# display.net
KiCad netlist of a schematic drawn in EAGLE
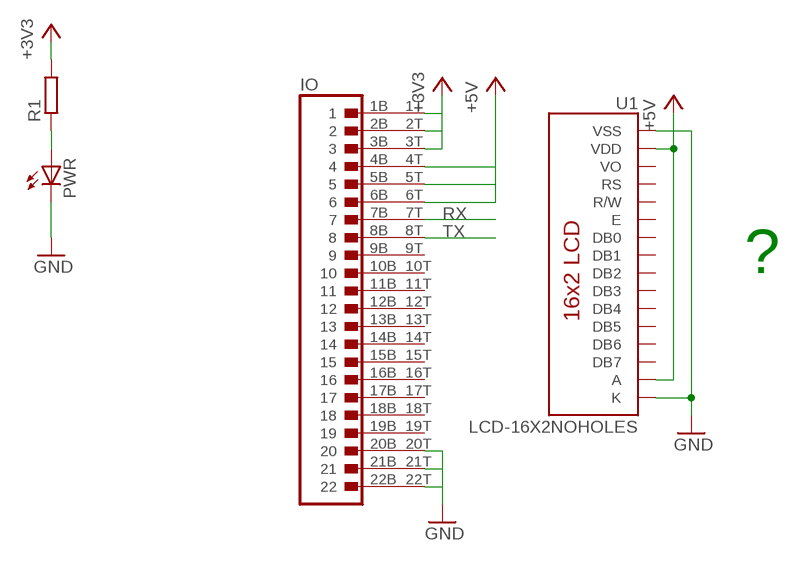
[diagram p0: schematic, sheet 1]

(export (version "E")
  (design (tool "Eeschema 10.0.6"))
  (components
    (comp (ref "IO")
      (value "SIMBRD22")
      (footprint "eagle-import:SIMBRD22")
      (libsource (lib "eagle-import") (part "SIMBRD22"))
    )
    (comp (ref "PWR")
      (value "LED1206")
      (footprint "eagle-import:LED-1206")
      (libsource (lib "eagle-import") (part "LED1206"))
    )
    (comp (ref "R1")
      (value "R-EU_R0805")
      (footprint "eagle-import:R0805")
      (libsource (lib "eagle-import") (part "R-EU_R0805"))
    )
    (comp (ref "U1")
      (value "LCD-16X2NOHOLES")
      (footprint "eagle-import:LCD-16X2_NOHOLES")
      (libsource (lib "eagle-import") (part "LCD-16X2NOHOLES"))
    )
  )
  (nets
    (net (code "1") (name "+3V3") (class "Default")
      (node (ref "IO") (pin "1T") (pinfunction "A1_1T") (pintype "passive"))
      (node (ref "IO") (pin "2T") (pinfunction "A2_2T") (pintype "passive"))
      (node (ref "IO") (pin "3T") (pinfunction "A3_3T") (pintype "passive"))
      (node (ref "R1") (pin "2") (pinfunction "2_2") (pintype "passive"))
    )
    (net (code "2") (name "+5V") (class "Default")
      (node (ref "IO") (pin "4T") (pinfunction "A4_4T") (pintype "passive"))
      (node (ref "IO") (pin "5T") (pinfunction "A5_5T") (pintype "passive"))
      (node (ref "IO") (pin "6T") (pinfunction "A6_6T") (pintype "passive"))
      (node (ref "U1") (pin "15") (pinfunction "A_15") (pintype "power_in"))
      (node (ref "U1") (pin "2") (pinfunction "VDD_2") (pintype "power_in"))
    )
    (net (code "3") (name "/RX") (class "Default")
      (node (ref "IO") (pin "7T") (pinfunction "A7_7T") (pintype "passive"))
    )
    (net (code "4") (name "/TX") (class "Default")
      (node (ref "IO") (pin "8T") (pinfunction "A8_8T") (pintype "passive"))
    )
    (net (code "5") (name "GND") (class "Default")
      (node (ref "IO") (pin "20T") (pinfunction "A20_20T") (pintype "passive"))
      (node (ref "IO") (pin "21T") (pinfunction "A21_21T") (pintype "passive"))
      (node (ref "IO") (pin "22T") (pinfunction "A22_22T") (pintype "passive"))
      (node (ref "PWR") (pin "C") (pinfunction "C_C") (pintype "passive"))
      (node (ref "U1") (pin "1") (pinfunction "VSS_1") (pintype "power_in"))
      (node (ref "U1") (pin "16") (pinfunction "K_16") (pintype "power_in"))
    )
    (net (code "6") (name "Net-(PWR-PadA)") (class "Default")
      (node (ref "PWR") (pin "A") (pinfunction "A_A") (pintype "passive"))
      (node (ref "R1") (pin "1") (pinfunction "1_1") (pintype "passive"))
    )
    (net (code "7") (name "unconnected-(IO-1-Pad1B)") (class "Default")
      (node (ref "IO") (pin "1B") (pinfunction "1_1B") (pintype "passive"))
    )
    (net (code "8") (name "unconnected-(IO-2-Pad2B)") (class "Default")
      (node (ref "IO") (pin "2B") (pinfunction "2_2B") (pintype "passive"))
    )
    (net (code "9") (name "unconnected-(IO-3-Pad3B)") (class "Default")
      (node (ref "IO") (pin "3B") (pinfunction "3_3B") (pintype "passive"))
    )
    (net (code "10") (name "unconnected-(IO-4-Pad4B)") (class "Default")
      (node (ref "IO") (pin "4B") (pinfunction "4_4B") (pintype "passive"))
    )
    (net (code "11") (name "unconnected-(IO-5-Pad5B)") (class "Default")
      (node (ref "IO") (pin "5B") (pinfunction "5_5B") (pintype "passive"))
    )
    (net (code "12") (name "unconnected-(IO-6-Pad6B)") (class "Default")
      (node (ref "IO") (pin "6B") (pinfunction "6_6B") (pintype "passive"))
    )
    (net (code "13") (name "unconnected-(IO-7-Pad7B)") (class "Default")
      (node (ref "IO") (pin "7B") (pinfunction "7_7B") (pintype "passive"))
    )
    (net (code "14") (name "unconnected-(IO-8-Pad8B)") (class "Default")
      (node (ref "IO") (pin "8B") (pinfunction "8_8B") (pintype "passive"))
    )
    (net (code "15") (name "unconnected-(IO-9-Pad9B)") (class "Default")
      (node (ref "IO") (pin "9B") (pinfunction "9_9B") (pintype "passive"))
    )
    (net (code "16") (name "unconnected-(IO-10-Pad10B)") (class "Default")
      (node (ref "IO") (pin "10B") (pinfunction "10_10B") (pintype "passive"))
    )
    (net (code "17") (name "unconnected-(IO-11-Pad11B)") (class "Default")
      (node (ref "IO") (pin "11B") (pinfunction "11_11B") (pintype "passive"))
    )
    (net (code "18") (name "unconnected-(IO-12-Pad12B)") (class "Default")
      (node (ref "IO") (pin "12B") (pinfunction "12_12B") (pintype "passive"))
    )
    (net (code "19") (name "unconnected-(IO-13-Pad13B)") (class "Default")
      (node (ref "IO") (pin "13B") (pinfunction "13_13B") (pintype "passive"))
    )
    (net (code "20") (name "unconnected-(IO-14-Pad14B)") (class "Default")
      (node (ref "IO") (pin "14B") (pinfunction "14_14B") (pintype "passive"))
    )
    (net (code "21") (name "unconnected-(IO-15-Pad15B)") (class "Default")
      (node (ref "IO") (pin "15B") (pinfunction "15_15B") (pintype "passive"))
    )
    (net (code "22") (name "unconnected-(IO-16-Pad16B)") (class "Default")
      (node (ref "IO") (pin "16B") (pinfunction "16_16B") (pintype "passive"))
    )
    (net (code "23") (name "unconnected-(IO-17-Pad17B)") (class "Default")
      (node (ref "IO") (pin "17B") (pinfunction "17_17B") (pintype "passive"))
    )
    (net (code "24") (name "unconnected-(IO-18-Pad18B)") (class "Default")
      (node (ref "IO") (pin "18B") (pinfunction "18_18B") (pintype "passive"))
    )
    (net (code "25") (name "unconnected-(IO-19-Pad19B)") (class "Default")
      (node (ref "IO") (pin "19B") (pinfunction "19_19B") (pintype "passive"))
    )
    (net (code "26") (name "unconnected-(IO-20-Pad20B)") (class "Default")
      (node (ref "IO") (pin "20B") (pinfunction "20_20B") (pintype "passive"))
    )
    (net (code "27") (name "unconnected-(IO-21-Pad21B)") (class "Default")
      (node (ref "IO") (pin "21B") (pinfunction "21_21B") (pintype "passive"))
    )
    (net (code "28") (name "unconnected-(IO-22-Pad22B)") (class "Default")
      (node (ref "IO") (pin "22B") (pinfunction "22_22B") (pintype "passive"))
    )
    (net (code "29") (name "unconnected-(IO-A9-Pad9T)") (class "Default")
      (node (ref "IO") (pin "9T") (pinfunction "A9_9T") (pintype "passive"))
    )
    (net (code "30") (name "unconnected-(IO-A10-Pad10T)") (class "Default")
      (node (ref "IO") (pin "10T") (pinfunction "A10_10T") (pintype "passive"))
    )
    (net (code "31") (name "unconnected-(IO-A11-Pad11T)") (class "Default")
      (node (ref "IO") (pin "11T") (pinfunction "A11_11T") (pintype "passive"))
    )
    (net (code "32") (name "unconnected-(IO-A12-Pad12T)") (class "Default")
      (node (ref "IO") (pin "12T") (pinfunction "A12_12T") (pintype "passive"))
    )
    (net (code "33") (name "unconnected-(IO-A13-Pad13T)") (class "Default")
      (node (ref "IO") (pin "13T") (pinfunction "A13_13T") (pintype "passive"))
    )
    (net (code "34") (name "unconnected-(IO-A14-Pad14T)") (class "Default")
      (node (ref "IO") (pin "14T") (pinfunction "A14_14T") (pintype "passive"))
    )
    (net (code "35") (name "unconnected-(IO-A15-Pad15T)") (class "Default")
      (node (ref "IO") (pin "15T") (pinfunction "A15_15T") (pintype "passive"))
    )
    (net (code "36") (name "unconnected-(IO-A16-Pad16T)") (class "Default")
      (node (ref "IO") (pin "16T") (pinfunction "A16_16T") (pintype "passive"))
    )
    (net (code "37") (name "unconnected-(IO-A17-Pad17T)") (class "Default")
      (node (ref "IO") (pin "17T") (pinfunction "A17_17T") (pintype "passive"))
    )
    (net (code "38") (name "unconnected-(IO-A18-Pad18T)") (class "Default")
      (node (ref "IO") (pin "18T") (pinfunction "A18_18T") (pintype "passive"))
    )
    (net (code "39") (name "unconnected-(IO-A19-Pad19T)") (class "Default")
      (node (ref "IO") (pin "19T") (pinfunction "A19_19T") (pintype "passive"))
    )
    (net (code "40") (name "unconnected-(U1-DB0-Pad7)") (class "Default")
      (node (ref "U1") (pin "7") (pinfunction "DB0_7") (pintype "bidirectional"))
    )
    (net (code "41") (name "unconnected-(U1-DB1-Pad8)") (class "Default")
      (node (ref "U1") (pin "8") (pinfunction "DB1_8") (pintype "bidirectional"))
    )
    (net (code "42") (name "unconnected-(U1-DB2-Pad9)") (class "Default")
      (node (ref "U1") (pin "9") (pinfunction "DB2_9") (pintype "bidirectional"))
    )
    (net (code "43") (name "unconnected-(U1-DB3-Pad10)") (class "Default")
      (node (ref "U1") (pin "10") (pinfunction "DB3_10") (pintype "bidirectional"))
    )
    (net (code "44") (name "unconnected-(U1-DB4-Pad11)") (class "Default")
      (node (ref "U1") (pin "11") (pinfunction "DB4_11") (pintype "bidirectional"))
    )
    (net (code "45") (name "unconnected-(U1-DB5-Pad12)") (class "Default")
      (node (ref "U1") (pin "12") (pinfunction "DB5_12") (pintype "bidirectional"))
    )
    (net (code "46") (name "unconnected-(U1-DB6-Pad13)") (class "Default")
      (node (ref "U1") (pin "13") (pinfunction "DB6_13") (pintype "bidirectional"))
    )
    (net (code "47") (name "unconnected-(U1-DB7-Pad14)") (class "Default")
      (node (ref "U1") (pin "14") (pinfunction "DB7_14") (pintype "bidirectional"))
    )
    (net (code "48") (name "unconnected-(U1-E-Pad6)") (class "Default")
      (node (ref "U1") (pin "6") (pinfunction "E_6") (pintype "input"))
    )
    (net (code "49") (name "unconnected-(U1-RS-Pad4)") (class "Default")
      (node (ref "U1") (pin "4") (pinfunction "RS_4") (pintype "input"))
    )
    (net (code "50") (name "unconnected-(U1-R{slash}W-Pad5)") (class "Default")
      (node (ref "U1") (pin "5") (pinfunction "R/W_5") (pintype "input"))
    )
    (net (code "51") (name "unconnected-(U1-VO-Pad3)") (class "Default")
      (node (ref "U1") (pin "3") (pinfunction "VO_3") (pintype "bidirectional"))
    )
  )
)
